# LCL_12V_chp.net
KiCad netlist of a schematic drawn in Altium Designer
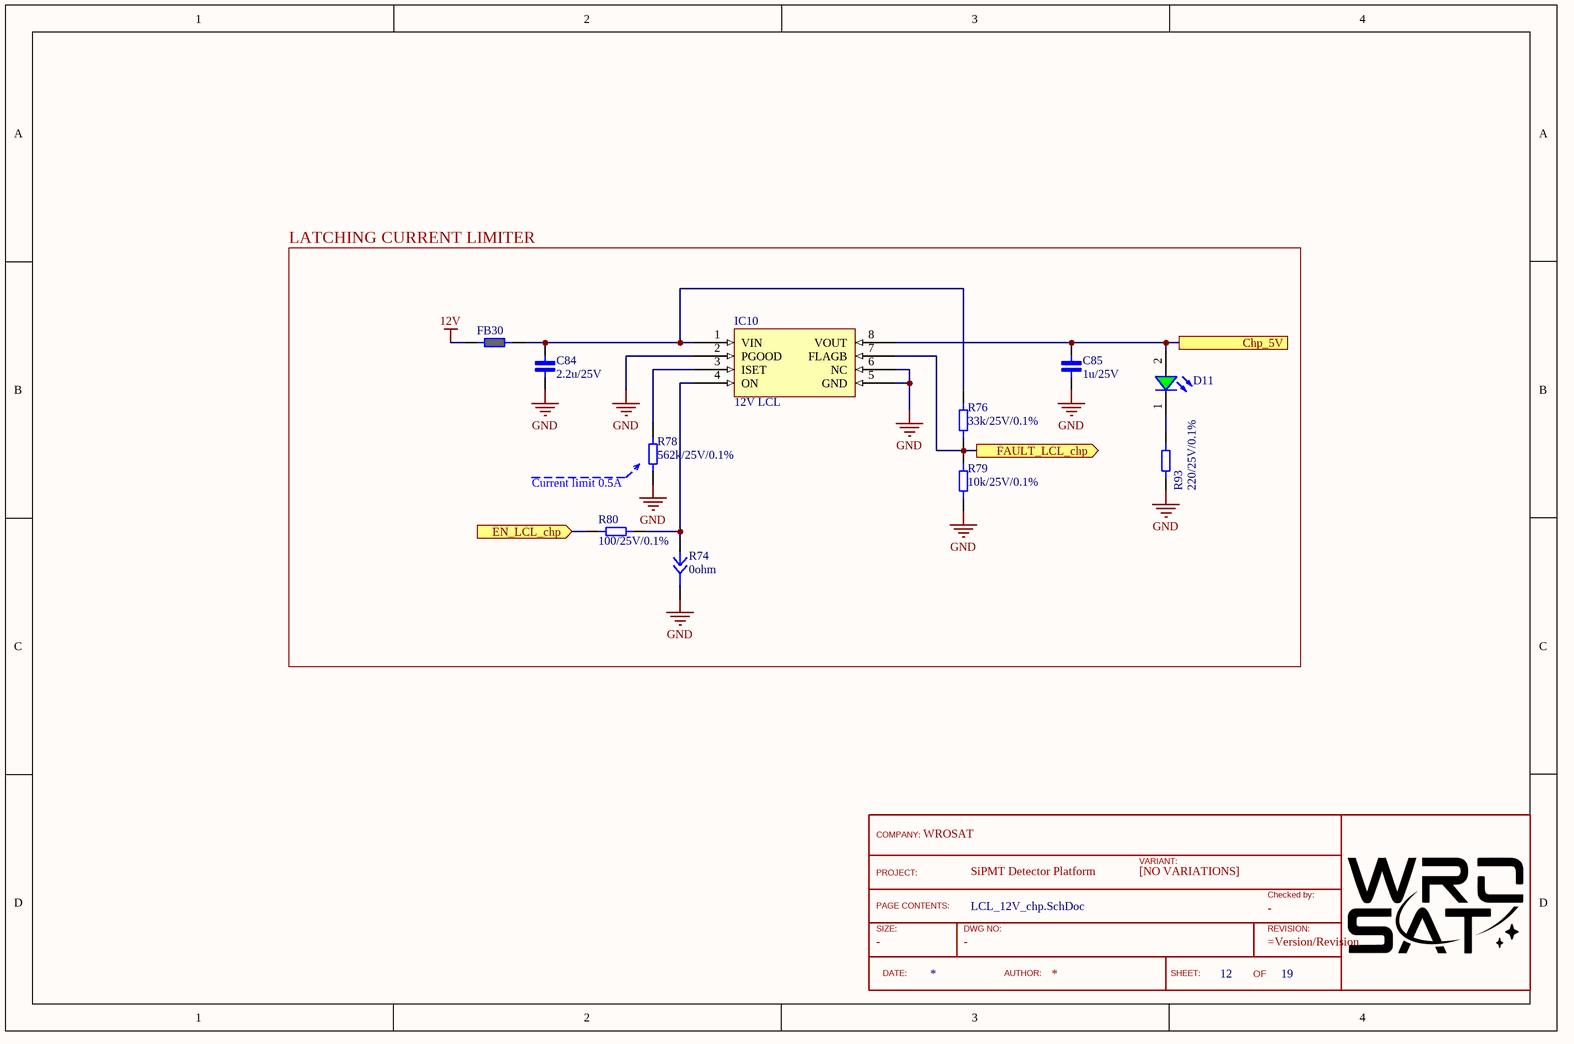
[diagram p0: LCL_12V_chp.SchDoc]

(export (version "E")
  (design (tool "Eeschema 10.0.6"))
  (components
    (comp (ref "C84")
      (value "2.2u/25V")
      (footprint "CAP_0603")
      (description "Ceramic Capacitor 2.2uF / 0603 / 25V / ±5%, Wurth Elektronik MLCC")
      (libsource (lib "Cubesat_lib") (part "Cap_0603_2.2u_25v"))
    )
    (comp (ref "C85")
      (value "1u/25V")
      (footprint "CAP_0603")
      (description "Ceramic Capacitor 1uF / 0603 / 25V / ±5%, Wurth Elektronik MLCC")
      (libsource (lib "Cubesat_lib") (part "Cap_0603_1u_25v"))
    )
    (comp (ref "D11")
      (value "Green, 3.2V")
      (footprint "WL-SMCW_0603_H=0.7mm")
      (description "WL-SMCW SMT Mono-color Chip LED Waterclear, size 0603, Green, 3.2V, 140deg")
      (fields (field (name "PART NUMBER") "150060GS75000") (field (name "PUBLISHER") "Wurth Elektronik"))
      (libsource (lib "LEDS") (part "150060GS75000"))
    )
    (comp (ref "FB30")
      (value "Ferrite_bead_0603")
      (footprint "Ferrite_0603")
      (description "Ferrite bead")
      (libsource (lib "Cubesat_lib") (part "Ferrite_bead_0603"))
    )
    (comp (ref "IC10")
      (value "12V LCL")
      (footprint "SO8")
      (description "FPF270xMX")
      (libsource (lib "Cubesat_lib") (part "FPF2700"))
    )
    (comp (ref "R74")
      (value "0ohm")
      (footprint "Jumper 2")
      (libsource (lib "Cubesat_lib") (part "Mini jumper"))
    )
    (comp (ref "R76")
      (value "33k/25V/0.1%")
      (footprint "RES_0402")
      (description "Vishay, thin film resistor 33k/25V/0.1%")
      (libsource (lib "Cubesat_lib") (part "Res_0402_33k"))
    )
    (comp (ref "R78")
      (value "562k/25V/0.1%")
      (footprint "RES_0402")
      (description "Vishay, thin film resistor 562k/25V/0.1%")
      (libsource (lib "Cubesat_lib") (part "Res_0402_562k"))
    )
    (comp (ref "R79")
      (value "10k/25V/0.1%")
      (footprint "RES_0402")
      (description "Vishay, thin film resistor 10k/25V/0.1%")
      (libsource (lib "Cubesat_lib") (part "Res_0402_10k"))
    )
    (comp (ref "R80")
      (value "100/25V/0.1%")
      (footprint "RES_0402")
      (description "Vishay, thin film resistor 100/25V/0.1%")
      (libsource (lib "Cubesat_lib") (part "Res_0402_100"))
    )
    (comp (ref "R93")
      (value "220/25V/0.1%")
      (footprint "RES_0402")
      (description "Vishay, thin film resistor 1/25V/0.1%")
      (libsource (lib "Cubesat_lib") (part "Res_0402_1"))
    )
  )
  (nets
    (net (code "1") (name "/Chp_5V") (class "Default")
      (node (ref "C85") (pin "2") (pinfunction "2_2") (pintype "passive"))
      (node (ref "D11") (pin "2") (pinfunction "A_2") (pintype "passive"))
      (node (ref "IC10") (pin "8") (pinfunction "VOUT_8") (pintype "input"))
    )
    (net (code "2") (name "/EN_LCL_chp") (class "Default")
      (node (ref "R80") (pin "2") (pinfunction "2_2") (pintype "passive"))
    )
    (net (code "3") (name "/FAULT_LCL_chp") (class "Default")
      (node (ref "IC10") (pin "7") (pinfunction "FLAGB_7") (pintype "input"))
      (node (ref "R76") (pin "1") (pinfunction "1_1") (pintype "passive"))
      (node (ref "R79") (pin "2") (pinfunction "2_2") (pintype "passive"))
    )
    (net (code "4") (name "12V") (class "Default")
      (node (ref "FB30") (pin "1") (pinfunction "1_1") (pintype "passive"))
    )
    (net (code "5") (name "GND") (class "Default")
      (node (ref "C84") (pin "1") (pinfunction "1_1") (pintype "passive"))
      (node (ref "C85") (pin "1") (pinfunction "1_1") (pintype "passive"))
      (node (ref "IC10") (pin "2") (pinfunction "PGOOD_2") (pintype "input"))
      (node (ref "IC10") (pin "5") (pinfunction "GND_5") (pintype "input"))
      (node (ref "IC10") (pin "6") (pinfunction "NC_6") (pintype "input"))
      (node (ref "R74") (pin "2") (pinfunction "2_2") (pintype "passive"))
      (node (ref "R78") (pin "1") (pinfunction "1_1") (pintype "passive"))
      (node (ref "R79") (pin "1") (pinfunction "1_1") (pintype "passive"))
      (node (ref "R93") (pin "1") (pinfunction "1_1") (pintype "passive"))
    )
    (net (code "6") (name "Net-(D11-K)") (class "Default")
      (node (ref "D11") (pin "1") (pinfunction "K_1") (pintype "passive"))
      (node (ref "R93") (pin "2") (pinfunction "2_2") (pintype "passive"))
    )
    (net (code "7") (name "Net-(IC10-ISET)") (class "Default")
      (node (ref "IC10") (pin "3") (pinfunction "ISET_3") (pintype "input"))
      (node (ref "R78") (pin "2") (pinfunction "2_2") (pintype "passive"))
    )
    (net (code "8") (name "Net-(IC10-ON)") (class "Default")
      (node (ref "IC10") (pin "4") (pinfunction "ON_4") (pintype "input"))
      (node (ref "R74") (pin "1") (pinfunction "1_1") (pintype "passive"))
      (node (ref "R80") (pin "1") (pinfunction "1_1") (pintype "passive"))
    )
    (net (code "9") (name "Net-(IC10-VIN)") (class "Default")
      (node (ref "C84") (pin "2") (pinfunction "2_2") (pintype "passive"))
      (node (ref "FB30") (pin "2") (pinfunction "2_2") (pintype "passive"))
      (node (ref "IC10") (pin "1") (pinfunction "VIN_1") (pintype "input"))
      (node (ref "R76") (pin "2") (pinfunction "2_2") (pintype "passive"))
    )
  )
)
